# hw2.net
KiCad netlist of a schematic drawn in EAGLE
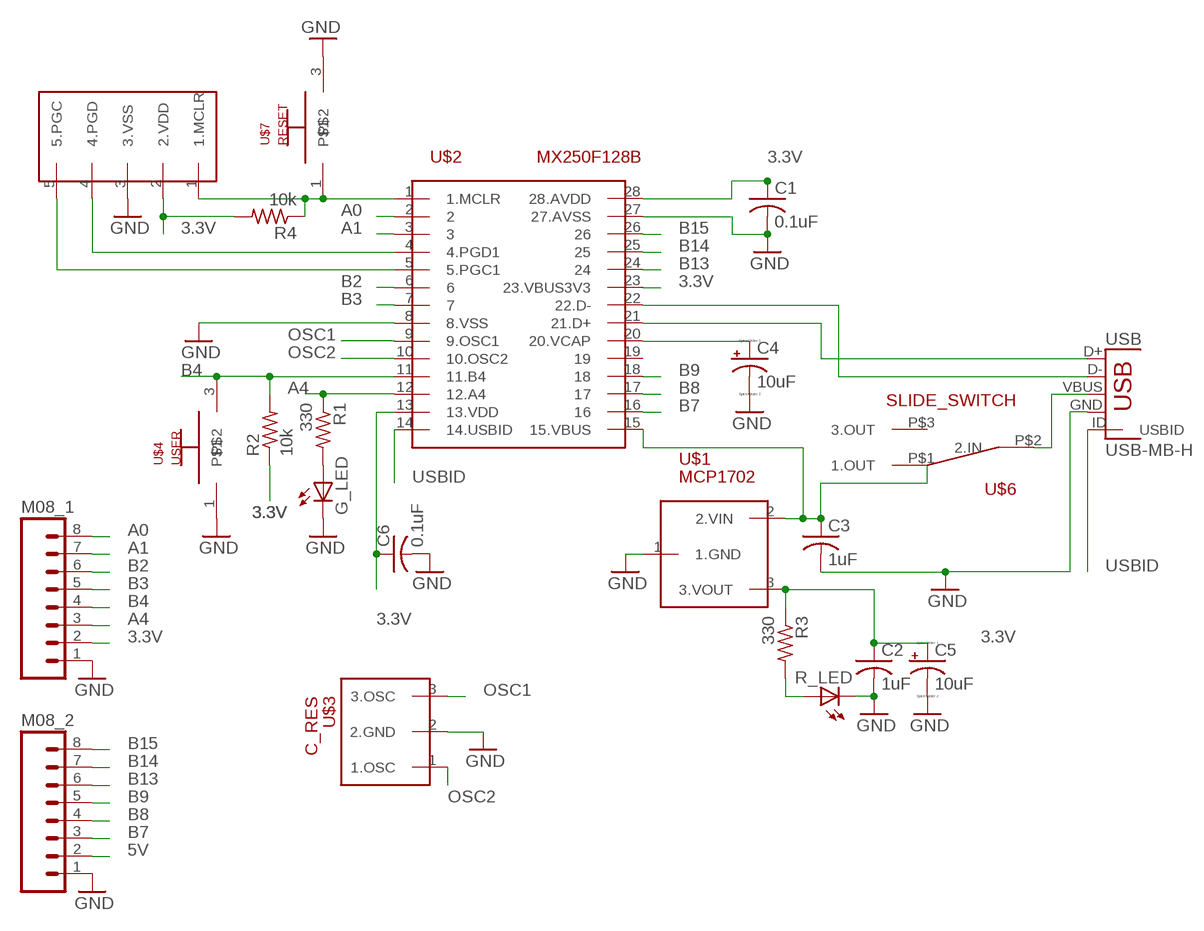
[diagram p0: schematic, sheet 1]

(export (version "E")
  (design (tool "Eeschema 10.0.6"))
  (components
    (comp (ref "C1")
      (value "0.1uF")
      (footprint "eagle-import:C025-025X050")
      (libsource (lib "eagle-import") (part "C-US025-025X050"))
    )
    (comp (ref "C2")
      (value "1uF")
      (footprint "eagle-import:C025-025X050")
      (libsource (lib "eagle-import") (part "C-US025-025X050"))
    )
    (comp (ref "C3")
      (value "1uF")
      (footprint "eagle-import:C025-025X050")
      (libsource (lib "eagle-import") (part "C-US025-025X050"))
    )
    (comp (ref "C4")
      (value "10uF")
      (footprint "eagle-import:E2,5-6E")
      (libsource (lib "eagle-import") (part "CPOL-USE2,5-6E"))
    )
    (comp (ref "C5")
      (value "10uF")
      (footprint "eagle-import:E2,5-6E")
      (libsource (lib "eagle-import") (part "CPOL-USE2,5-6E"))
    )
    (comp (ref "C6")
      (value "0.1uF")
      (footprint "eagle-import:C025-025X050")
      (libsource (lib "eagle-import") (part "C-US025-025X050"))
    )
    (comp (ref "G_LED")
      (value "LED3MM")
      (footprint "eagle-import:LED3MM")
      (libsource (lib "eagle-import") (part "LED3MM"))
    )
    (comp (ref "M08_1")
      (value "M08")
      (footprint "eagle-import:1X08_ROUND")
      (libsource (lib "eagle-import") (part "M08"))
    )
    (comp (ref "M08_2")
      (value "M08")
      (footprint "eagle-import:1X08_ROUND")
      (libsource (lib "eagle-import") (part "M08"))
    )
    (comp (ref "R1")
      (value "330")
      (footprint "eagle-import:0207_10")
      (libsource (lib "eagle-import") (part "resistor_R-US_0207/10"))
    )
    (comp (ref "R2")
      (value "10k")
      (footprint "eagle-import:0207_10")
      (libsource (lib "eagle-import") (part "R-US_0207/10"))
    )
    (comp (ref "R3")
      (value "330")
      (footprint "eagle-import:0207_10")
      (libsource (lib "eagle-import") (part "resistor_R-US_0207/10"))
    )
    (comp (ref "R4")
      (value "10k")
      (footprint "eagle-import:0207_10")
      (libsource (lib "eagle-import") (part "resistor_R-US_0207/10"))
    )
    (comp (ref "R_LED")
      (value "LED3MM")
      (footprint "eagle-import:LED3MM")
      (libsource (lib "eagle-import") (part "LED3MM"))
    )
    (comp (ref "U$1")
      (value "MCP1702")
      (footprint "eagle-import:TO92")
      (libsource (lib "eagle-import") (part "MCP1702"))
    )
    (comp (ref "U$2")
      (value "MX250F128B")
      (footprint "eagle-import:DIL28-3")
      (libsource (lib "eagle-import") (part "MX250F128B"))
    )
    (comp (ref "U$3")
      (value "C_RES")
      (footprint "eagle-import:1X03")
      (libsource (lib "eagle-import") (part "C_RES"))
    )
    (comp (ref "U$4")
      (value "USER")
      (footprint "eagle-import:1X03")
      (libsource (lib "eagle-import") (part "BUTTON"))
    )
    (comp (ref "U$5")
      (value "PICKIT3")
      (footprint "eagle-import:1X05")
      (libsource (lib "eagle-import") (part "PICKIT3"))
    )
    (comp (ref "U$6")
      (value "SLIDE_SWITCH")
      (footprint "eagle-import:SLIDE_SWITCH")
      (libsource (lib "eagle-import") (part "SLIDE_SWITCH"))
    )
    (comp (ref "U$7")
      (value "RESET")
      (footprint "eagle-import:1X03")
      (libsource (lib "eagle-import") (part "BUTTON"))
    )
    (comp (ref "USB")
      (value "USB-MB-H")
      (footprint "eagle-import:USB-MB-H")
      (libsource (lib "eagle-import") (part "USB-MB-H"))
    )
  )
  (nets
    (net (code "1") (name "/3.3V") (class "Default")
      (node (ref "C1") (pin "1") (pinfunction "1_1") (pintype "passive"))
      (node (ref "C2") (pin "1") (pinfunction "1_1") (pintype "passive"))
      (node (ref "C5") (pin "+") (pinfunction "+_+") (pintype "passive"))
      (node (ref "C6") (pin "1") (pinfunction "1_1") (pintype "passive"))
      (node (ref "M08_1") (pin "2") (pinfunction "2_2") (pintype "passive"))
      (node (ref "R2") (pin "1") (pinfunction "1_1") (pintype "passive"))
      (node (ref "R3") (pin "1") (pinfunction "1_1") (pintype "passive"))
      (node (ref "R4") (pin "2") (pinfunction "2_2") (pintype "passive"))
      (node (ref "U$1") (pin "3") (pinfunction "3.VOUT_3") (pintype "bidirectional"))
      (node (ref "U$2") (pin "13") (pinfunction "13.VDD_13") (pintype "bidirectional"))
      (node (ref "U$2") (pin "23") (pinfunction "23.VBUS3V3_23") (pintype "bidirectional"))
      (node (ref "U$2") (pin "28") (pinfunction "28.AVDD_28") (pintype "bidirectional"))
      (node (ref "U$5") (pin "2") (pinfunction "2.VDD_2") (pintype "bidirectional"))
    )
    (net (code "2") (name "/5V") (class "Default")
      (node (ref "C3") (pin "1") (pinfunction "1_1") (pintype "passive"))
      (node (ref "M08_2") (pin "2") (pinfunction "2_2") (pintype "passive"))
      (node (ref "U$1") (pin "2") (pinfunction "2.VIN_2") (pintype "bidirectional"))
      (node (ref "U$2") (pin "15") (pinfunction "15.VBUS_15") (pintype "bidirectional"))
      (node (ref "U$2") (pin "22") (pinfunction "22.D-_22") (pintype "bidirectional"))
      (node (ref "U$6") (pin "P$1") (pinfunction "1.OUT_P$1") (pintype "bidirectional"))
      (node (ref "USB") (pin "D-") (pinfunction "D-_D-") (pintype "bidirectional"))
    )
    (net (code "3") (name "/A0") (class "Default")
      (node (ref "M08_1") (pin "8") (pinfunction "8_8") (pintype "passive"))
      (node (ref "U$2") (pin "2") (pinfunction "2_2") (pintype "bidirectional"))
    )
    (net (code "4") (name "/A1") (class "Default")
      (node (ref "M08_1") (pin "7") (pinfunction "7_7") (pintype "passive"))
      (node (ref "U$2") (pin "3") (pinfunction "3_3") (pintype "bidirectional"))
    )
    (net (code "5") (name "/A4") (class "Default")
      (node (ref "M08_1") (pin "3") (pinfunction "3_3") (pintype "passive"))
      (node (ref "R1") (pin "1") (pinfunction "1_1") (pintype "passive"))
      (node (ref "U$2") (pin "12") (pinfunction "12.A4_12") (pintype "bidirectional"))
    )
    (net (code "6") (name "/B2") (class "Default")
      (node (ref "M08_1") (pin "6") (pinfunction "6_6") (pintype "passive"))
      (node (ref "U$2") (pin "6") (pinfunction "6_6") (pintype "bidirectional"))
    )
    (net (code "7") (name "/B3") (class "Default")
      (node (ref "M08_1") (pin "5") (pinfunction "5_5") (pintype "passive"))
      (node (ref "U$2") (pin "7") (pinfunction "7_7") (pintype "bidirectional"))
    )
    (net (code "8") (name "/B4") (class "Default")
      (node (ref "M08_1") (pin "4") (pinfunction "4_4") (pintype "passive"))
      (node (ref "R2") (pin "2") (pinfunction "2_2") (pintype "passive"))
      (node (ref "U$2") (pin "11") (pinfunction "11.B4_11") (pintype "bidirectional"))
      (node (ref "U$4") (pin "3") (pinfunction "P$2_3") (pintype "bidirectional"))
    )
    (net (code "9") (name "/B7") (class "Default")
      (node (ref "M08_2") (pin "3") (pinfunction "3_3") (pintype "passive"))
      (node (ref "U$2") (pin "16") (pinfunction "16_16") (pintype "bidirectional"))
    )
    (net (code "10") (name "/B8") (class "Default")
      (node (ref "M08_2") (pin "4") (pinfunction "4_4") (pintype "passive"))
      (node (ref "U$2") (pin "17") (pinfunction "17_17") (pintype "bidirectional"))
    )
    (net (code "11") (name "/B9") (class "Default")
      (node (ref "M08_2") (pin "5") (pinfunction "5_5") (pintype "passive"))
      (node (ref "U$2") (pin "18") (pinfunction "18_18") (pintype "bidirectional"))
    )
    (net (code "12") (name "/B13") (class "Default")
      (node (ref "M08_2") (pin "6") (pinfunction "6_6") (pintype "passive"))
      (node (ref "U$2") (pin "24") (pinfunction "24_24") (pintype "bidirectional"))
    )
    (net (code "13") (name "/B14") (class "Default")
      (node (ref "M08_2") (pin "7") (pinfunction "7_7") (pintype "passive"))
      (node (ref "U$2") (pin "25") (pinfunction "25_25") (pintype "bidirectional"))
    )
    (net (code "14") (name "/B15") (class "Default")
      (node (ref "M08_2") (pin "8") (pinfunction "8_8") (pintype "passive"))
      (node (ref "U$2") (pin "26") (pinfunction "26_26") (pintype "bidirectional"))
    )
    (net (code "15") (name "/OSC1") (class "Default")
      (node (ref "U$2") (pin "9") (pinfunction "9.OSC1_9") (pintype "bidirectional"))
      (node (ref "U$3") (pin "3") (pinfunction "3.OSC_3") (pintype "bidirectional"))
    )
    (net (code "16") (name "/OSC2") (class "Default")
      (node (ref "U$2") (pin "10") (pinfunction "10.OSC2_10") (pintype "bidirectional"))
      (node (ref "U$3") (pin "1") (pinfunction "1.OSC_1") (pintype "bidirectional"))
    )
    (net (code "17") (name "/USBID") (class "Default")
      (node (ref "U$2") (pin "14") (pinfunction "14.USBID_14") (pintype "bidirectional"))
      (node (ref "USB") (pin "ID") (pinfunction "USBID_ID") (pintype "bidirectional"))
    )
    (net (code "18") (name "GND") (class "Default")
      (node (ref "C1") (pin "2") (pinfunction "2_2") (pintype "passive"))
      (node (ref "C2") (pin "2") (pinfunction "2_2") (pintype "passive"))
      (node (ref "C3") (pin "2") (pinfunction "2_2") (pintype "passive"))
      (node (ref "C4") (pin "-") (pinfunction "-_-") (pintype "passive"))
      (node (ref "C5") (pin "-") (pinfunction "-_-") (pintype "passive"))
      (node (ref "C6") (pin "2") (pinfunction "2_2") (pintype "passive"))
      (node (ref "G_LED") (pin "K") (pinfunction "C_K") (pintype "passive"))
      (node (ref "M08_1") (pin "1") (pinfunction "1_1") (pintype "passive"))
      (node (ref "M08_2") (pin "1") (pinfunction "1_1") (pintype "passive"))
      (node (ref "R_LED") (pin "K") (pinfunction "C_K") (pintype "passive"))
      (node (ref "U$1") (pin "1") (pinfunction "1.GND_1") (pintype "bidirectional"))
      (node (ref "U$2") (pin "27") (pinfunction "27.AVSS_27") (pintype "bidirectional"))
      (node (ref "U$2") (pin "8") (pinfunction "8.VSS_8") (pintype "bidirectional"))
      (node (ref "U$3") (pin "2") (pinfunction "2.GND_2") (pintype "bidirectional"))
      (node (ref "U$4") (pin "1") (pinfunction "P$1_1") (pintype "bidirectional"))
      (node (ref "U$5") (pin "3") (pinfunction "3.VSS_3") (pintype "bidirectional"))
      (node (ref "U$7") (pin "3") (pinfunction "P$2_3") (pintype "bidirectional"))
      (node (ref "USB") (pin "GND") (pinfunction "GND_GND") (pintype "bidirectional"))
    )
    (net (code "19") (name "Net-(G_LED-PadA)") (class "Default")
      (node (ref "G_LED") (pin "A") (pinfunction "A_A") (pintype "passive"))
      (node (ref "R1") (pin "2") (pinfunction "2_2") (pintype "passive"))
    )
    (net (code "20") (name "Net-(R3-Pad2)") (class "Default")
      (node (ref "R3") (pin "2") (pinfunction "2_2") (pintype "passive"))
      (node (ref "R_LED") (pin "A") (pinfunction "A_A") (pintype "passive"))
    )
    (net (code "21") (name "Net-(U$2-1.MCLR)") (class "Default")
      (node (ref "R4") (pin "1") (pinfunction "1_1") (pintype "passive"))
      (node (ref "U$2") (pin "1") (pinfunction "1.MCLR_1") (pintype "bidirectional"))
      (node (ref "U$5") (pin "1") (pinfunction "1.MCLR_1") (pintype "bidirectional"))
      (node (ref "U$7") (pin "1") (pinfunction "P$1_1") (pintype "bidirectional"))
    )
    (net (code "22") (name "Net-(U$2-4.PGD1)") (class "Default")
      (node (ref "U$2") (pin "4") (pinfunction "4.PGD1_4") (pintype "bidirectional"))
      (node (ref "U$5") (pin "4") (pinfunction "4.PGD_4") (pintype "bidirectional"))
    )
    (net (code "23") (name "Net-(U$2-5.PGC1)") (class "Default")
      (node (ref "U$2") (pin "5") (pinfunction "5.PGC1_5") (pintype "bidirectional"))
      (node (ref "U$5") (pin "5") (pinfunction "5.PGC_5") (pintype "bidirectional"))
    )
    (net (code "24") (name "Net-(U$2-20.VCAP)") (class "Default")
      (node (ref "C4") (pin "+") (pinfunction "+_+") (pintype "passive"))
      (node (ref "U$2") (pin "20") (pinfunction "20.VCAP_20") (pintype "bidirectional"))
    )
    (net (code "25") (name "Net-(U$2-21.D+)") (class "Default")
      (node (ref "U$2") (pin "21") (pinfunction "21.D+_21") (pintype "bidirectional"))
      (node (ref "USB") (pin "D+") (pinfunction "D+_D+") (pintype "bidirectional"))
    )
    (net (code "26") (name "Net-(U$6-2.IN)") (class "Default")
      (node (ref "U$6") (pin "P$2") (pinfunction "2.IN_P$2") (pintype "bidirectional"))
      (node (ref "USB") (pin "VBUS") (pinfunction "VBUS_VBUS") (pintype "bidirectional"))
    )
    (net (code "27") (name "unconnected-(U$2-Pad19)") (class "Default")
      (node (ref "U$2") (pin "19") (pinfunction "19_19") (pintype "bidirectional"))
    )
    (net (code "28") (name "unconnected-(U$6-3.OUT-PadP$3)") (class "Default")
      (node (ref "U$6") (pin "P$3") (pinfunction "3.OUT_P$3") (pintype "bidirectional"))
    )
  )
)
